# EasyEDA_Schematics.net
KiCad netlist of a schematic drawn in EasyEDA
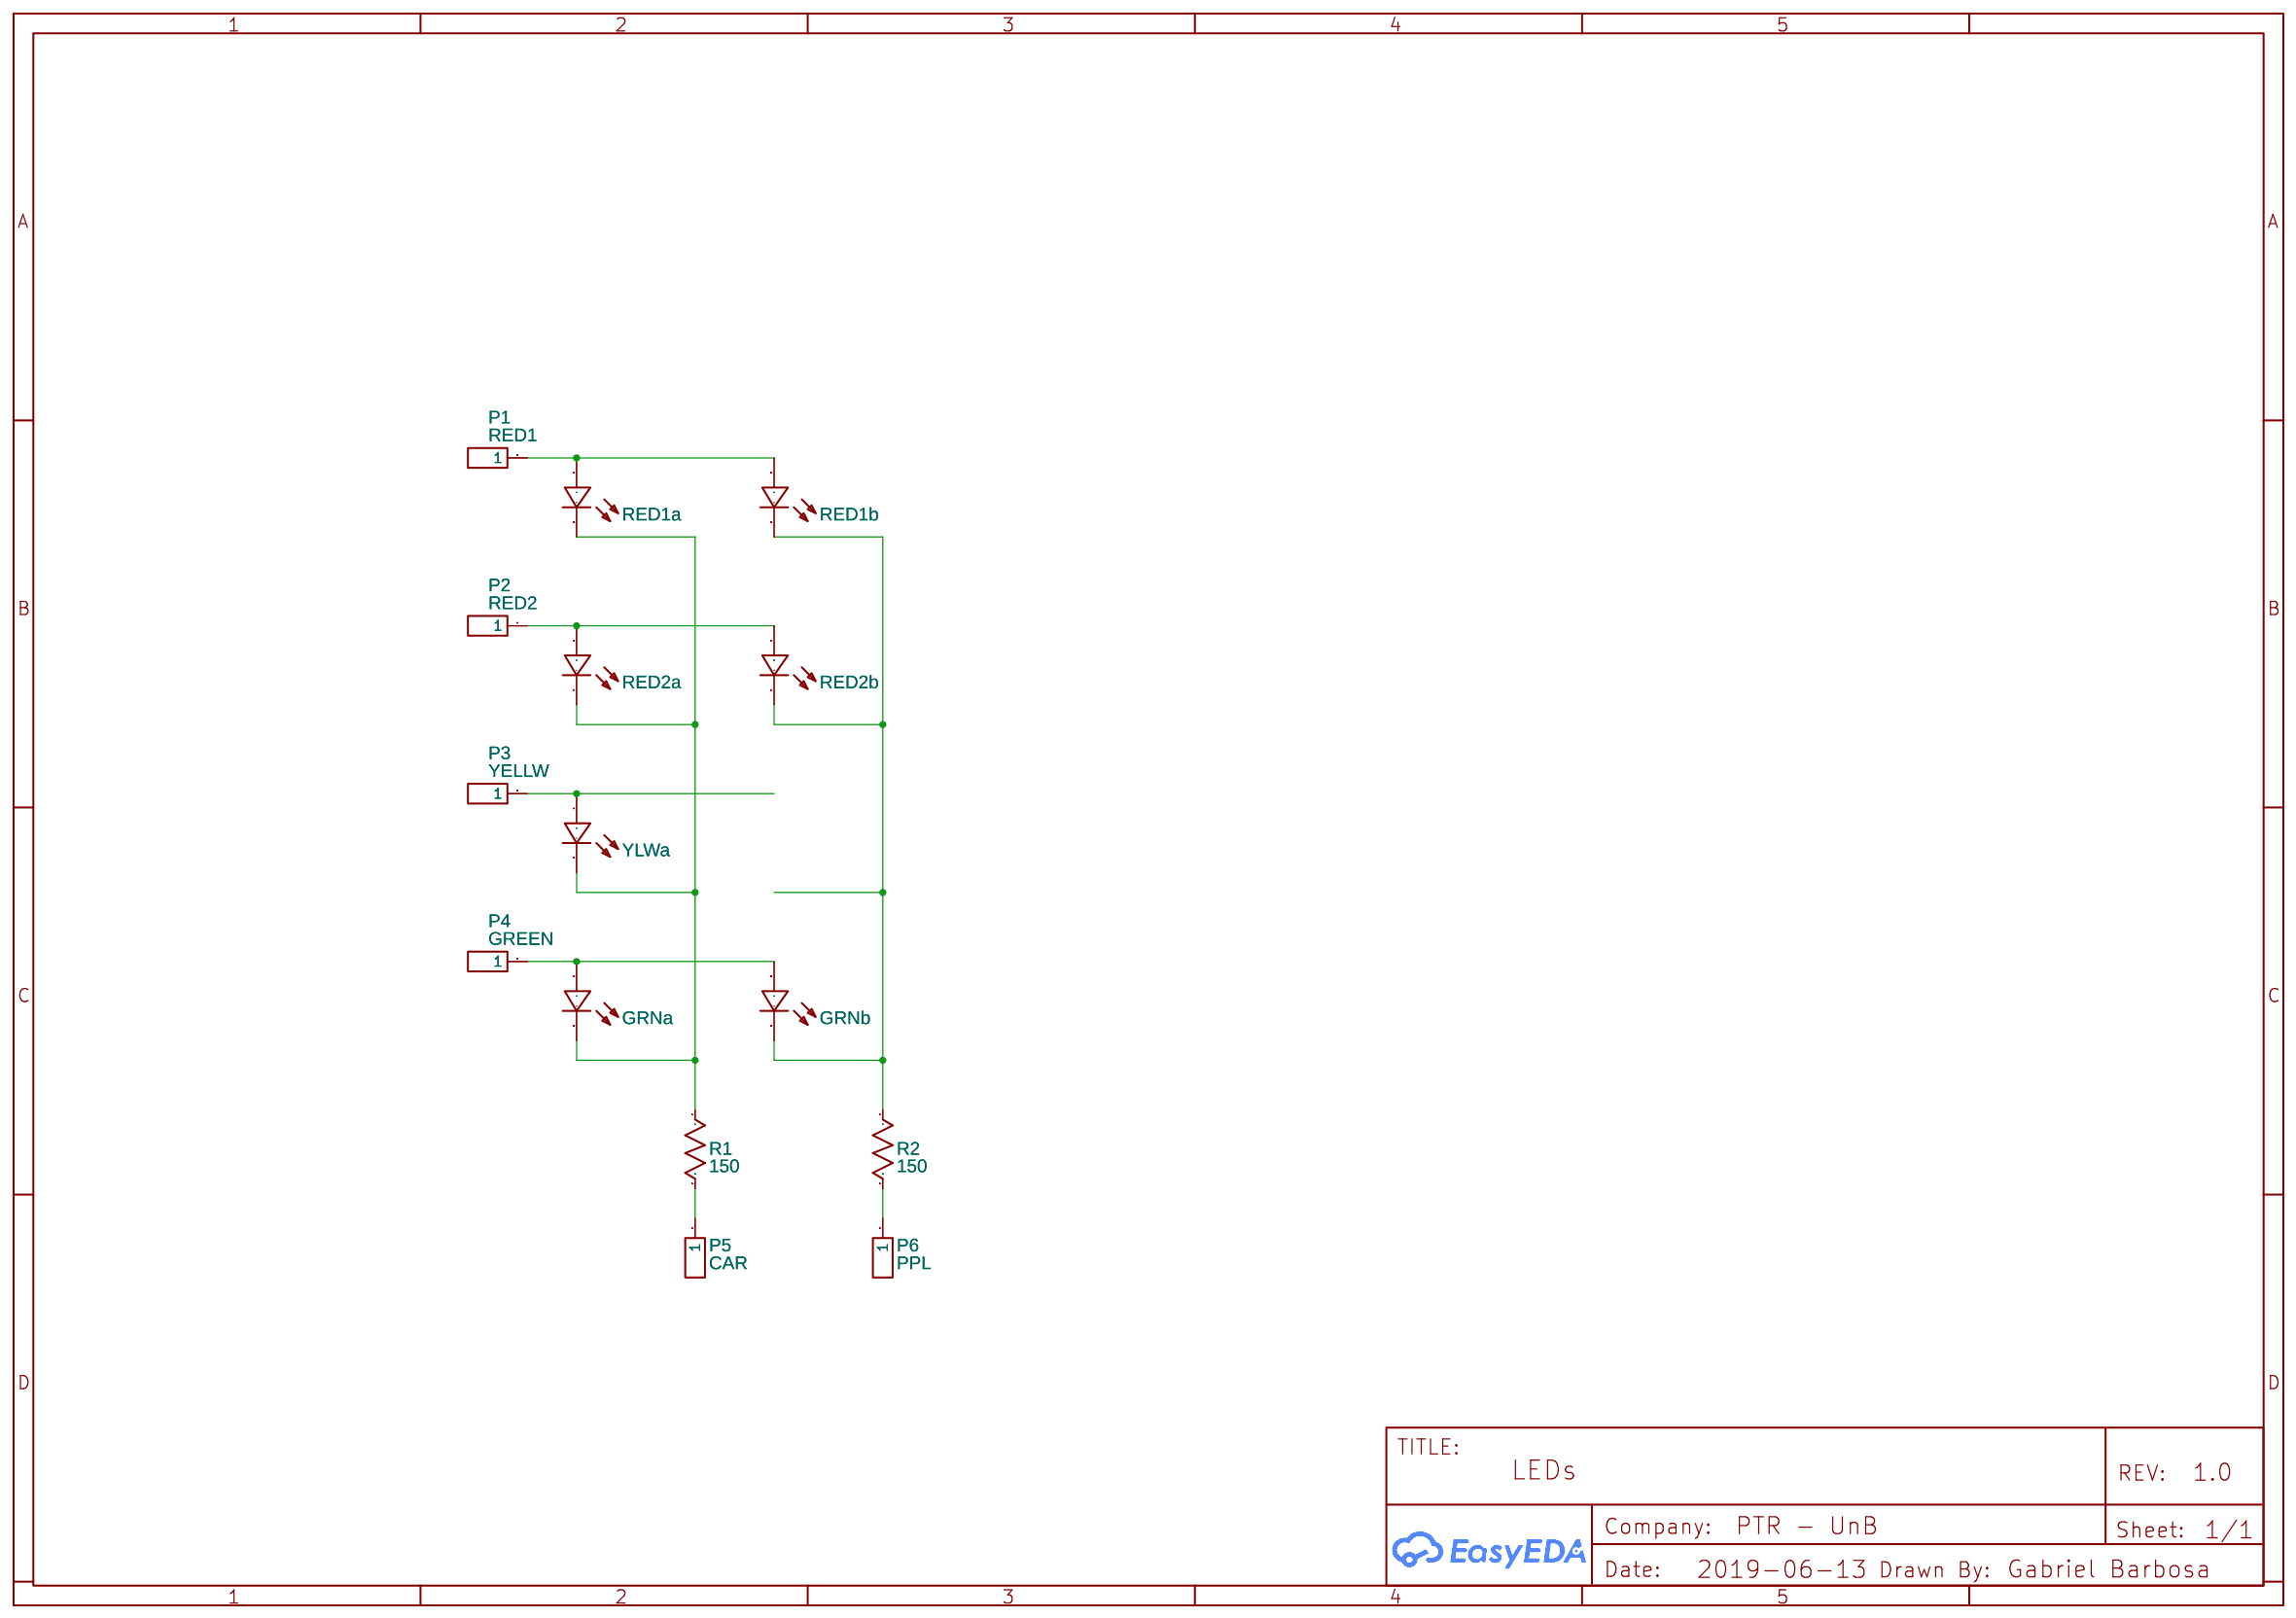
[diagram p0: schematic sheet]

(export (version "E")
  (design (tool "Eeschema 10.0.6"))
  (components
    (comp (ref "LED1")
      (value "RED1a")
      (fields
        (field (name "BOM_Manufacturer Part") "204-10SURD/S530-A3")
        (field (name "BOM_Supplier Part") "C99772")
      )
      (libsource (lib "") (part "Unknown_290_245"))
    )
    (comp (ref "LED2")
      (value "RED1b")
      (fields
        (field (name "BOM_Manufacturer Part") "204-10SURD/S530-A3")
        (field (name "BOM_Supplier Part") "C99772")
      )
      (libsource (lib "") (part "Unknown_390_245"))
    )
    (comp (ref "LED3")
      (value "RED2a")
      (fields
        (field (name "BOM_Manufacturer Part") "204-10SURD/S530-A3")
        (field (name "BOM_Supplier Part") "C99772")
      )
      (libsource (lib "") (part "Unknown_290_330"))
    )
    (comp (ref "LED4")
      (value "RED2b")
      (fields
        (field (name "BOM_Manufacturer Part") "204-10SURD/S530-A3")
        (field (name "BOM_Supplier Part") "C99772")
      )
      (libsource (lib "") (part "Unknown_390_330"))
    )
    (comp (ref "LED5")
      (value "YLWa")
      (fields
        (field (name "BOM_Manufacturer Part") "204-10SURD/S530-A3")
        (field (name "BOM_Supplier Part") "C99772")
      )
      (libsource (lib "") (part "Unknown_290_415"))
    )
    (comp (ref "LED7")
      (value "GRNa")
      (fields
        (field (name "BOM_Manufacturer Part") "204-10SURD/S530-A3")
        (field (name "BOM_Supplier Part") "C99772")
      )
      (libsource (lib "") (part "Unknown_290_500"))
    )
    (comp (ref "LED8")
      (value "GRNb")
      (fields
        (field (name "BOM_Manufacturer Part") "204-10SURD/S530-A3")
        (field (name "BOM_Supplier Part") "C99772")
      )
      (libsource (lib "") (part "Unknown_390_500"))
    )
    (comp (ref "P1")
      (value "RED1")
      (fields
        (field (name "BOM_Manufacturer Part") "Header-Male-2.54_1x1")
        (field (name "BOM_Supplier Part") "C81276")
      )
      (libsource (lib "") (part "Unknown_245_225"))
    )
    (comp (ref "P2")
      (value "RED2")
      (fields
        (field (name "BOM_Manufacturer Part") "Header-Male-2.54_1x1")
        (field (name "BOM_Supplier Part") "C81276")
      )
      (libsource (lib "") (part "Unknown_245_310"))
    )
    (comp (ref "P3")
      (value "YELLW")
      (fields
        (field (name "BOM_Manufacturer Part") "Header-Male-2.54_1x1")
        (field (name "BOM_Supplier Part") "C81276")
      )
      (libsource (lib "") (part "Unknown_245_395"))
    )
    (comp (ref "P4")
      (value "GREEN")
      (fields
        (field (name "BOM_Manufacturer Part") "Header-Male-2.54_1x1")
        (field (name "BOM_Supplier Part") "C81276")
      )
      (libsource (lib "") (part "Unknown_245_480"))
    )
    (comp (ref "P5")
      (value "CAR")
      (fields
        (field (name "BOM_Manufacturer Part") "Header-Male-2.54_1x1")
        (field (name "BOM_Supplier Part") "C81276")
      )
      (libsource (lib "") (part "Unknown_345_625"))
    )
    (comp (ref "P6")
      (value "PPL")
      (fields
        (field (name "BOM_Manufacturer Part") "Header-Male-2.54_1x1")
        (field (name "BOM_Supplier Part") "C81276")
      )
      (libsource (lib "") (part "Unknown_440_625"))
    )
    (comp (ref "R1")
      (value "150")
      (fields (field (name "BOM_Manufacturer Part") "?"))
      (libsource (lib "") (part "Res_AXIAL-0.3(1/8W)_US"))
    )
    (comp (ref "R2")
      (value "150")
      (fields (field (name "BOM_Manufacturer Part") "?"))
      (libsource (lib "") (part "Res_AXIAL-0.3(1/8W)_US"))
    )
  )
  (nets
    (net (code "1") (name "Net-(LED1-+)") (class "Default")
      (node (ref "LED1") (pin "1") (pinfunction "+_1") (pintype "unspecified"))
      (node (ref "LED2") (pin "1") (pinfunction "+_1") (pintype "unspecified"))
      (node (ref "P1") (pin "1") (pinfunction "1_1") (pintype "input"))
    )
    (net (code "2") (name "Net-(LED1--)") (class "Default")
      (node (ref "LED1") (pin "2") (pinfunction "-_2") (pintype "unspecified"))
      (node (ref "LED3") (pin "2") (pinfunction "-_2") (pintype "unspecified"))
      (node (ref "LED5") (pin "2") (pinfunction "-_2") (pintype "unspecified"))
      (node (ref "LED7") (pin "2") (pinfunction "-_2") (pintype "unspecified"))
      (node (ref "R1") (pin "1") (pinfunction "1_1") (pintype "unspecified"))
    )
    (net (code "3") (name "Net-(LED2--)") (class "Default")
      (node (ref "LED2") (pin "2") (pinfunction "-_2") (pintype "unspecified"))
      (node (ref "LED4") (pin "2") (pinfunction "-_2") (pintype "unspecified"))
      (node (ref "LED8") (pin "2") (pinfunction "-_2") (pintype "unspecified"))
      (node (ref "R2") (pin "1") (pinfunction "1_1") (pintype "unspecified"))
    )
    (net (code "4") (name "Net-(LED3-+)") (class "Default")
      (node (ref "LED3") (pin "1") (pinfunction "+_1") (pintype "unspecified"))
      (node (ref "LED4") (pin "1") (pinfunction "+_1") (pintype "unspecified"))
      (node (ref "P2") (pin "1") (pinfunction "1_1") (pintype "input"))
    )
    (net (code "5") (name "Net-(LED5-+)") (class "Default")
      (node (ref "LED5") (pin "1") (pinfunction "+_1") (pintype "unspecified"))
      (node (ref "P3") (pin "1") (pinfunction "1_1") (pintype "input"))
    )
    (net (code "6") (name "Net-(LED7-+)") (class "Default")
      (node (ref "LED7") (pin "1") (pinfunction "+_1") (pintype "unspecified"))
      (node (ref "LED8") (pin "1") (pinfunction "+_1") (pintype "unspecified"))
      (node (ref "P4") (pin "1") (pinfunction "1_1") (pintype "input"))
    )
    (net (code "7") (name "Net-(P5-Pad1)") (class "Default")
      (node (ref "P5") (pin "1") (pinfunction "1_1") (pintype "input"))
      (node (ref "R1") (pin "2") (pinfunction "2_2") (pintype "unspecified"))
    )
    (net (code "8") (name "Net-(P6-Pad1)") (class "Default")
      (node (ref "P6") (pin "1") (pinfunction "1_1") (pintype "input"))
      (node (ref "R2") (pin "2") (pinfunction "2_2") (pintype "unspecified"))
    )
  )
)
